# DRIVER_B.net
KiCad netlist of a schematic drawn in Altium Designer
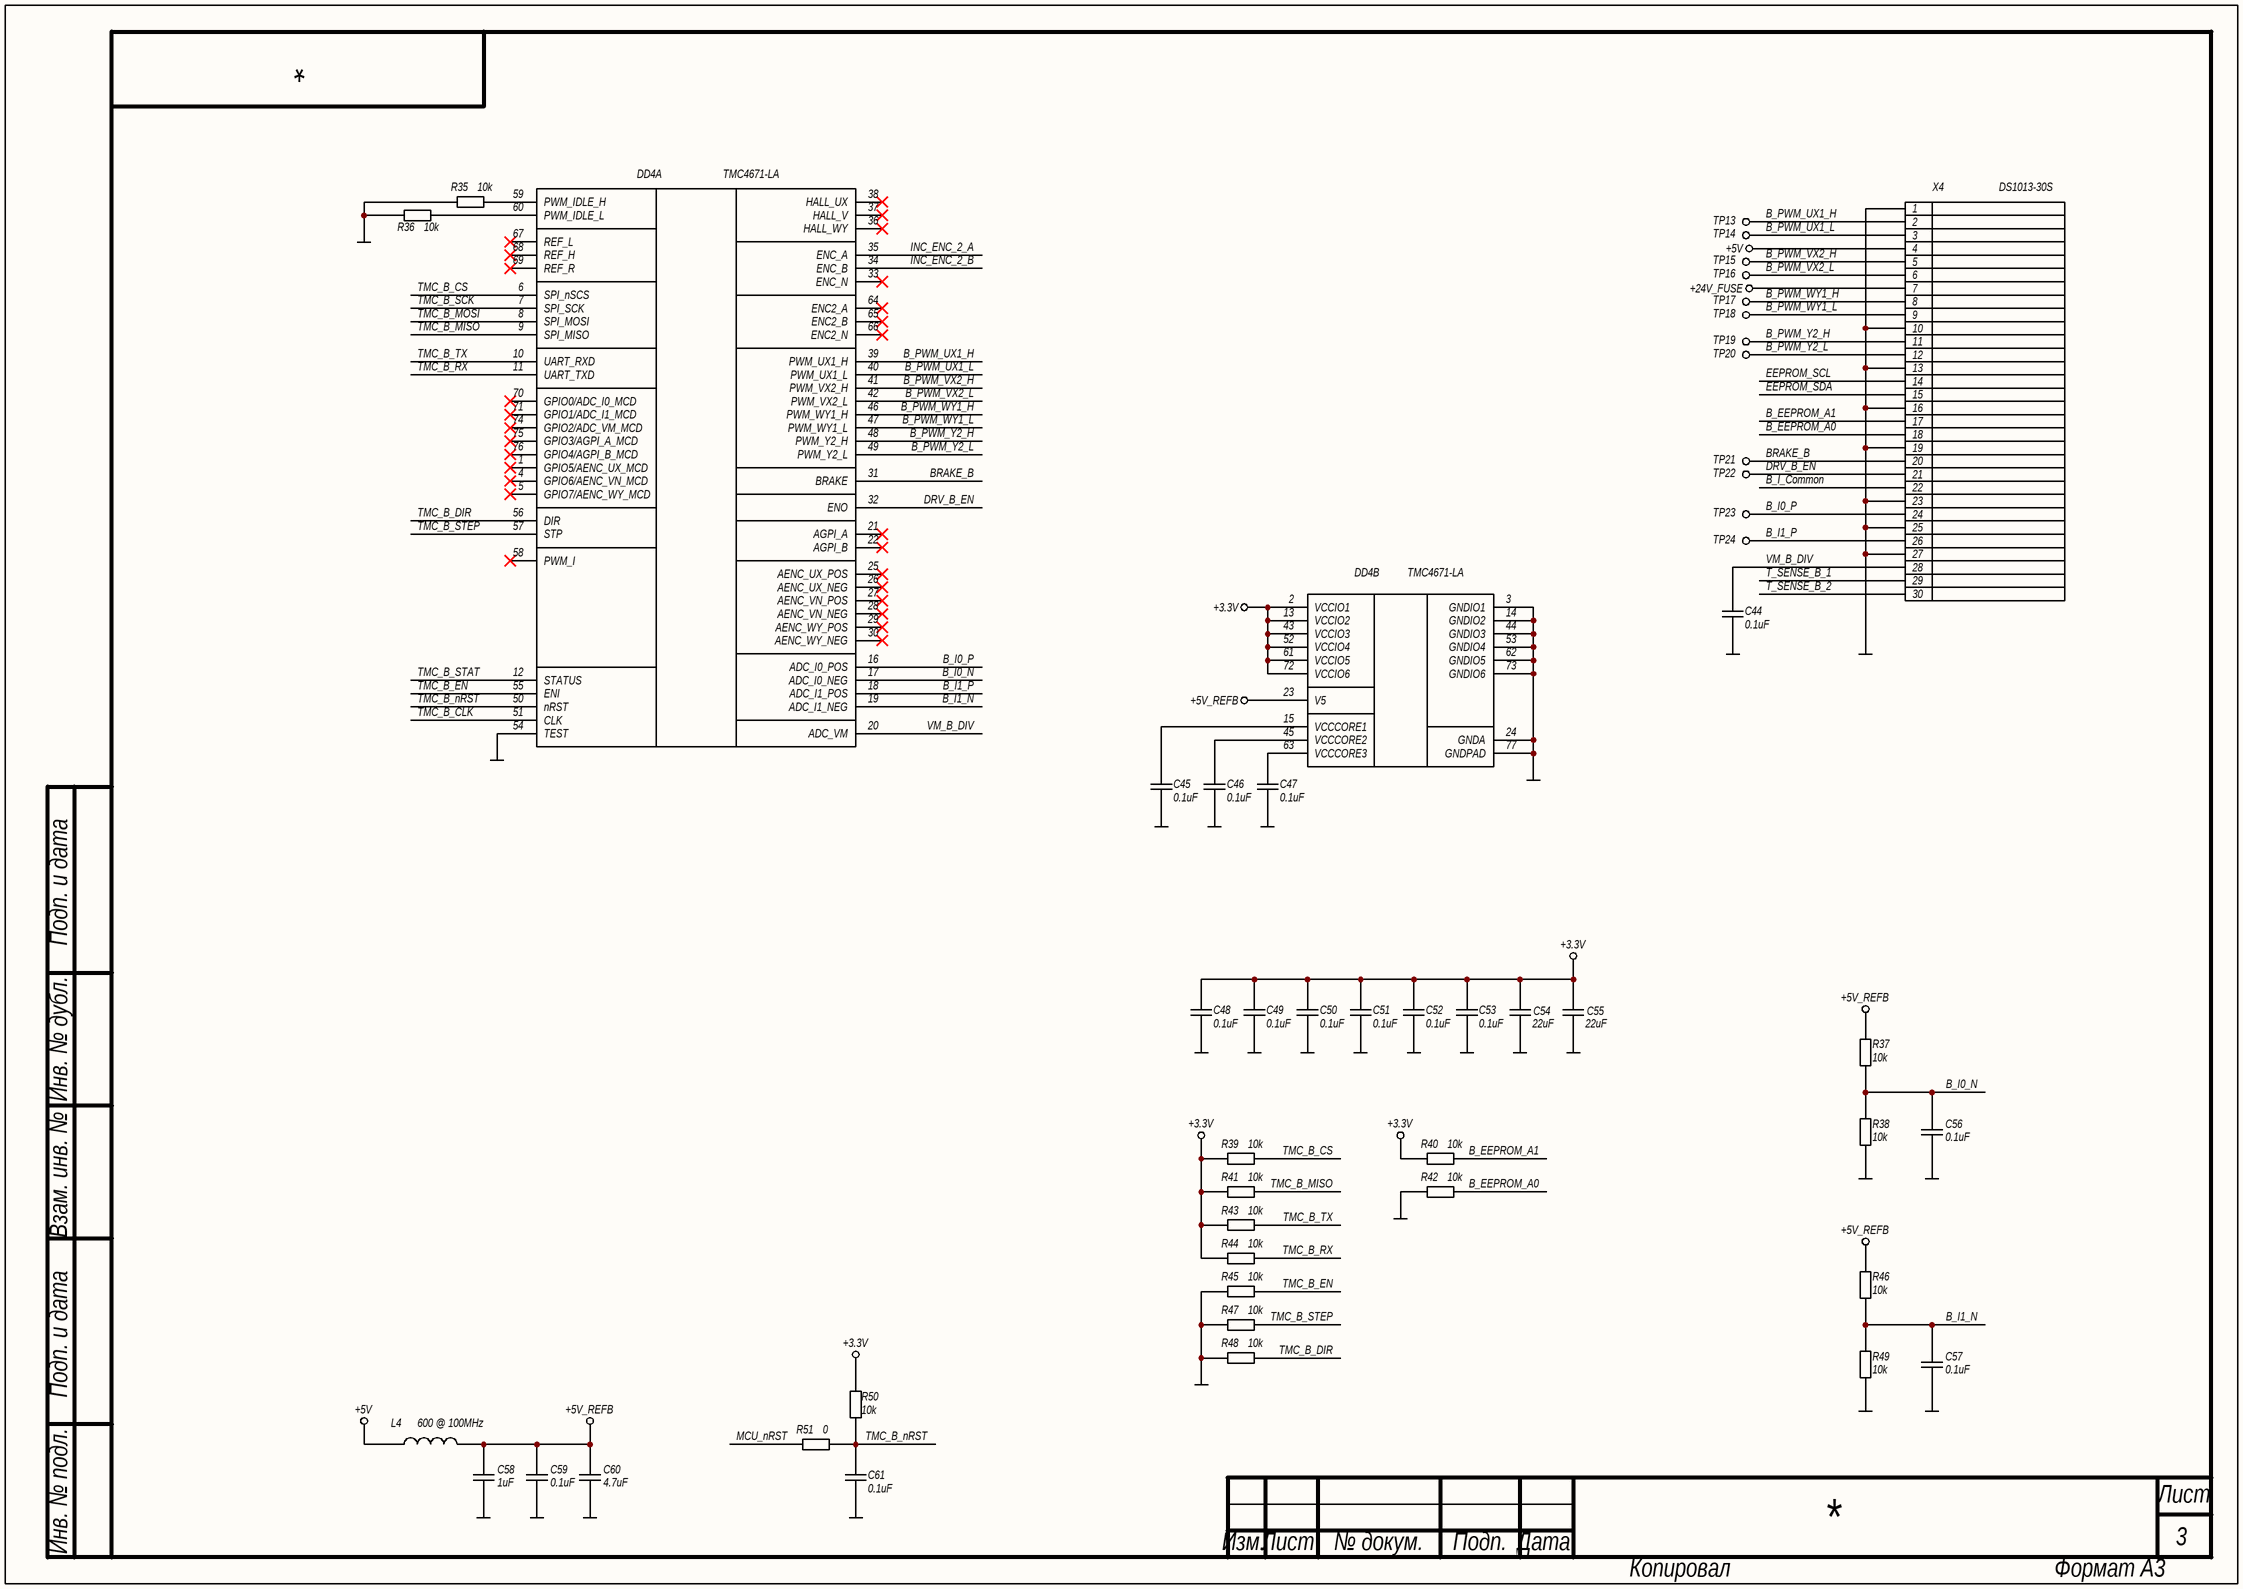
[diagram p0: DRIVER_B.SchDoc]

(export (version "E")
  (design (tool "Eeschema 10.0.6"))
  (components
    (comp (ref "C44")
      (value "0.1uF")
      (footprint "C0603N")
      (description "Конденсатор")
      (libsource (lib "Components Library") (part "CAP_FIXED"))
    )
    (comp (ref "C45")
      (value "0.1uF")
      (footprint "C0603N")
      (description "Конденсатор")
      (libsource (lib "Components Library") (part "CAP_FIXED"))
    )
    (comp (ref "C46")
      (value "0.1uF")
      (footprint "C0603N")
      (description "Конденсатор")
      (libsource (lib "Components Library") (part "CAP_FIXED"))
    )
    (comp (ref "C47")
      (value "0.1uF")
      (footprint "C0603N")
      (description "Конденсатор")
      (libsource (lib "Components Library") (part "CAP_FIXED"))
    )
    (comp (ref "C48")
      (value "0.1uF")
      (footprint "C0603N")
      (description "Конденсатор")
      (libsource (lib "Components Library") (part "CAP_FIXED"))
    )
    (comp (ref "C49")
      (value "0.1uF")
      (footprint "C0603N")
      (description "Конденсатор")
      (libsource (lib "Components Library") (part "CAP_FIXED"))
    )
    (comp (ref "C50")
      (value "0.1uF")
      (footprint "C0603N")
      (description "Конденсатор")
      (libsource (lib "Components Library") (part "CAP_FIXED"))
    )
    (comp (ref "C51")
      (value "0.1uF")
      (footprint "C0603N")
      (description "Конденсатор")
      (libsource (lib "Components Library") (part "CAP_FIXED"))
    )
    (comp (ref "C52")
      (value "0.1uF")
      (footprint "C0603N")
      (description "Конденсатор")
      (libsource (lib "Components Library") (part "CAP_FIXED"))
    )
    (comp (ref "C53")
      (value "0.1uF")
      (footprint "C0603N")
      (description "Конденсатор")
      (libsource (lib "Components Library") (part "CAP_FIXED"))
    )
    (comp (ref "C54")
      (value "22uF")
      (footprint "C0805N")
      (description "Конденсатор")
      (libsource (lib "Components Library") (part "CAP_FIXED"))
    )
    (comp (ref "C55")
      (value "22uF")
      (footprint "C0805N")
      (description "Конденсатор")
      (libsource (lib "Components Library") (part "CAP_FIXED"))
    )
    (comp (ref "C56")
      (value "0.1uF")
      (footprint "C0603N")
      (description "Конденсатор")
      (libsource (lib "Components Library") (part "CAP_FIXED"))
    )
    (comp (ref "C57")
      (value "0.1uF")
      (footprint "C0603N")
      (description "Конденсатор")
      (libsource (lib "Components Library") (part "CAP_FIXED"))
    )
    (comp (ref "C58")
      (value "1uF")
      (footprint "C0603N")
      (description "Конденсатор")
      (libsource (lib "Components Library") (part "CAP_FIXED"))
    )
    (comp (ref "C59")
      (value "0.1uF")
      (footprint "C0603N")
      (description "Конденсатор")
      (libsource (lib "Components Library") (part "CAP_FIXED"))
    )
    (comp (ref "C60")
      (value "4.7uF")
      (footprint "C0603N")
      (description "Конденсатор")
      (libsource (lib "Components Library") (part "CAP_FIXED"))
    )
    (comp (ref "C61")
      (value "0.1uF")
      (footprint "C0603N")
      (description "Конденсатор")
      (libsource (lib "Components Library") (part "CAP_FIXED"))
    )
    (comp (ref "DD4")
      (value "TMC4671-LA")
      (footprint "QFN76-EP")
      (description "Микросхема драйвер двигателя")
      (libsource (lib "Components Library") (part "TMC4671-LA"))
    )
    (comp (ref "L4")
      (value "600 @ 100MHz")
      (footprint "FB0603N")
      (description "Фильтр ЭМП индуктивный")
      (libsource (lib "Components Library") (part "IND_FILTER"))
    )
    (comp (ref "R35")
      (value "10k")
      (footprint "R0603N")
      (description "Резистор")
      (libsource (lib "Components Library") (part "RES_FIXED"))
    )
    (comp (ref "R36")
      (value "10k")
      (footprint "R0603N")
      (description "Резистор")
      (libsource (lib "Components Library") (part "RES_FIXED"))
    )
    (comp (ref "R37")
      (value "10k")
      (footprint "R0603N")
      (description "Резистор")
      (libsource (lib "") (part "RES_FIXED_1"))
    )
    (comp (ref "R38")
      (value "10k")
      (footprint "R0603N")
      (description "Резистор")
      (libsource (lib "") (part "RES_FIXED_1"))
    )
    (comp (ref "R39")
      (value "10k")
      (footprint "R0603N")
      (description "Резистор")
      (libsource (lib "Components Library") (part "RES_FIXED"))
    )
    (comp (ref "R40")
      (value "10k")
      (footprint "R0603N")
      (description "Резистор")
      (libsource (lib "Components Library") (part "RES_FIXED"))
    )
    (comp (ref "R41")
      (value "10k")
      (footprint "R0603N")
      (description "Резистор")
      (libsource (lib "Components Library") (part "RES_FIXED"))
    )
    (comp (ref "R42")
      (value "10k")
      (footprint "R0603N")
      (description "Резистор")
      (libsource (lib "Components Library") (part "RES_FIXED"))
    )
    (comp (ref "R43")
      (value "10k")
      (footprint "R0603N")
      (description "Резистор")
      (libsource (lib "Components Library") (part "RES_FIXED"))
    )
    (comp (ref "R44")
      (value "10k")
      (footprint "R0603N")
      (description "Резистор")
      (libsource (lib "Components Library") (part "RES_FIXED"))
    )
    (comp (ref "R45")
      (value "10k")
      (footprint "R0603N")
      (description "Резистор")
      (libsource (lib "Components Library") (part "RES_FIXED"))
    )
    (comp (ref "R46")
      (value "10k")
      (footprint "R0603N")
      (description "Резистор")
      (libsource (lib "") (part "RES_FIXED_1"))
    )
    (comp (ref "R47")
      (value "10k")
      (footprint "R0603N")
      (description "Резистор")
      (libsource (lib "Components Library") (part "RES_FIXED"))
    )
    (comp (ref "R48")
      (value "10k")
      (footprint "R0603N")
      (description "Резистор")
      (libsource (lib "Components Library") (part "RES_FIXED"))
    )
    (comp (ref "R49")
      (value "10k")
      (footprint "R0603N")
      (description "Резистор")
      (libsource (lib "") (part "RES_FIXED_1"))
    )
    (comp (ref "R50")
      (value "10k")
      (footprint "R0603N")
      (description "Резистор")
      (libsource (lib "") (part "RES_FIXED_1"))
    )
    (comp (ref "R51")
      (value "0")
      (footprint "R0603N")
      (description "Резистор")
      (libsource (lib "Components Library") (part "RES_FIXED"))
    )
    (comp (ref "TP13")
      (value "TEST_POINT")
      (footprint "TP_RPAD_0.8MM")
      (description "Контрольная точка")
      (libsource (lib "Components Library") (part "TEST_POINT"))
    )
    (comp (ref "TP14")
      (value "TEST_POINT")
      (footprint "TP_RPAD_0.8MM")
      (description "Контрольная точка")
      (libsource (lib "Components Library") (part "TEST_POINT"))
    )
    (comp (ref "TP15")
      (value "TEST_POINT")
      (footprint "TP_RPAD_0.8MM")
      (description "Контрольная точка")
      (libsource (lib "Components Library") (part "TEST_POINT"))
    )
    (comp (ref "TP16")
      (value "TEST_POINT")
      (footprint "TP_RPAD_0.8MM")
      (description "Контрольная точка")
      (libsource (lib "Components Library") (part "TEST_POINT"))
    )
    (comp (ref "TP17")
      (value "TEST_POINT")
      (footprint "TP_RPAD_0.8MM")
      (description "Контрольная точка")
      (libsource (lib "Components Library") (part "TEST_POINT"))
    )
    (comp (ref "TP18")
      (value "TEST_POINT")
      (footprint "TP_RPAD_0.8MM")
      (description "Контрольная точка")
      (libsource (lib "Components Library") (part "TEST_POINT"))
    )
    (comp (ref "TP19")
      (value "TEST_POINT")
      (footprint "TP_RPAD_0.8MM")
      (description "Контрольная точка")
      (libsource (lib "Components Library") (part "TEST_POINT"))
    )
    (comp (ref "TP20")
      (value "TEST_POINT")
      (footprint "TP_RPAD_0.8MM")
      (description "Контрольная точка")
      (libsource (lib "Components Library") (part "TEST_POINT"))
    )
    (comp (ref "TP21")
      (value "TEST_POINT")
      (footprint "TP_RPAD_0.8MM")
      (description "Контрольная точка")
      (libsource (lib "Components Library") (part "TEST_POINT"))
    )
    (comp (ref "TP22")
      (value "TEST_POINT")
      (footprint "TP_RPAD_0.8MM")
      (description "Контрольная точка")
      (libsource (lib "Components Library") (part "TEST_POINT"))
    )
    (comp (ref "TP23")
      (value "TEST_POINT")
      (footprint "TP_RPAD_0.8MM")
      (description "Контрольная точка")
      (libsource (lib "Components Library") (part "TEST_POINT"))
    )
    (comp (ref "TP24")
      (value "TEST_POINT")
      (footprint "TP_RPAD_0.8MM")
      (description "Контрольная точка")
      (libsource (lib "Components Library") (part "TEST_POINT"))
    )
    (comp (ref "X4")
      (value "DS1013-30S")
      (footprint "2.54_2X15_HEADER_BOX")
      (description "Разъем, 30 контактов")
      (libsource (lib "Components Library") (part "Connector 30"))
    )
  )
  (nets
    (net (code "1") (name "+3.3V") (class "Default")
      (node (ref "C48") (pin "2") (pinfunction "2_2") (pintype "passive"))
      (node (ref "C49") (pin "2") (pinfunction "2_2") (pintype "passive"))
      (node (ref "C50") (pin "2") (pinfunction "2_2") (pintype "passive"))
      (node (ref "C51") (pin "2") (pinfunction "2_2") (pintype "passive"))
      (node (ref "C52") (pin "2") (pinfunction "2_2") (pintype "passive"))
      (node (ref "C53") (pin "2") (pinfunction "2_2") (pintype "passive"))
      (node (ref "C54") (pin "2") (pinfunction "2_2") (pintype "passive"))
      (node (ref "C55") (pin "2") (pinfunction "2_2") (pintype "passive"))
      (node (ref "DD4") (pin "13") (pinfunction "VCCIO2_13") (pintype "power_in"))
      (node (ref "DD4") (pin "2") (pinfunction "VCCIO1_2") (pintype "power_in"))
      (node (ref "DD4") (pin "43") (pinfunction "VCCIO3_43") (pintype "power_in"))
      (node (ref "DD4") (pin "52") (pinfunction "VCCIO4_52") (pintype "power_in"))
      (node (ref "DD4") (pin "61") (pinfunction "VCCIO5_61") (pintype "power_in"))
      (node (ref "DD4") (pin "72") (pinfunction "VCCIO6_72") (pintype "power_in"))
      (node (ref "R39") (pin "2") (pinfunction "2_2") (pintype "passive"))
      (node (ref "R40") (pin "2") (pinfunction "2_2") (pintype "passive"))
      (node (ref "R41") (pin "2") (pinfunction "2_2") (pintype "passive"))
      (node (ref "R43") (pin "2") (pinfunction "2_2") (pintype "passive"))
      (node (ref "R44") (pin "2") (pinfunction "2_2") (pintype "passive"))
      (node (ref "R50") (pin "2") (pinfunction "2_2") (pintype "passive"))
    )
    (net (code "2") (name "+5V") (class "Default")
      (node (ref "L4") (pin "1") (pinfunction "1_1") (pintype "passive"))
      (node (ref "X4") (pin "4") (pinfunction "4_4") (pintype "power_in"))
    )
    (net (code "3") (name "+5V_REFB") (class "Default")
      (node (ref "C58") (pin "2") (pinfunction "2_2") (pintype "passive"))
      (node (ref "C59") (pin "2") (pinfunction "2_2") (pintype "passive"))
      (node (ref "C60") (pin "2") (pinfunction "2_2") (pintype "passive"))
      (node (ref "DD4") (pin "23") (pinfunction "V5_23") (pintype "power_in"))
      (node (ref "L4") (pin "2") (pinfunction "2_2") (pintype "passive"))
      (node (ref "R37") (pin "2") (pinfunction "2_2") (pintype "passive"))
      (node (ref "R46") (pin "2") (pinfunction "2_2") (pintype "passive"))
    )
    (net (code "4") (name "+24V_FUSE") (class "Default")
      (node (ref "X4") (pin "7") (pinfunction "7_7") (pintype "power_in"))
    )
    (net (code "5") (name "/BRAKE_B") (class "Default")
      (node (ref "DD4") (pin "31") (pinfunction "BRAKE_31") (pintype "power_in"))
      (node (ref "TP21") (pin "1") (pinfunction "1_1") (pintype "passive"))
      (node (ref "X4") (pin "20") (pinfunction "20_20") (pintype "power_in"))
    )
    (net (code "6") (name "/B_EEPROM_A0") (class "Default")
      (node (ref "R42") (pin "1") (pinfunction "1_1") (pintype "passive"))
      (node (ref "X4") (pin "18") (pinfunction "18_18") (pintype "power_in"))
    )
    (net (code "7") (name "/B_EEPROM_A1") (class "Default")
      (node (ref "R40") (pin "1") (pinfunction "1_1") (pintype "passive"))
      (node (ref "X4") (pin "17") (pinfunction "17_17") (pintype "power_in"))
    )
    (net (code "8") (name "/B_I0_N") (class "Default")
      (node (ref "C56") (pin "2") (pinfunction "2_2") (pintype "passive"))
      (node (ref "DD4") (pin "17") (pinfunction "ADC_I0_NEG_17") (pintype "power_in"))
      (node (ref "R37") (pin "1") (pinfunction "1_1") (pintype "passive"))
      (node (ref "R38") (pin "2") (pinfunction "2_2") (pintype "passive"))
    )
    (net (code "9") (name "/B_I0_P") (class "Default")
      (node (ref "DD4") (pin "16") (pinfunction "ADC_I0_POS_16") (pintype "power_in"))
      (node (ref "TP23") (pin "1") (pinfunction "1_1") (pintype "passive"))
      (node (ref "X4") (pin "24") (pinfunction "24_24") (pintype "power_in"))
    )
    (net (code "10") (name "/B_I1_N") (class "Default")
      (node (ref "C57") (pin "2") (pinfunction "2_2") (pintype "passive"))
      (node (ref "DD4") (pin "19") (pinfunction "ADC_I1_NEG_19") (pintype "power_in"))
      (node (ref "R46") (pin "1") (pinfunction "1_1") (pintype "passive"))
      (node (ref "R49") (pin "2") (pinfunction "2_2") (pintype "passive"))
    )
    (net (code "11") (name "/B_I1_P") (class "Default")
      (node (ref "DD4") (pin "18") (pinfunction "ADC_I1_POS_18") (pintype "power_in"))
      (node (ref "TP24") (pin "1") (pinfunction "1_1") (pintype "passive"))
      (node (ref "X4") (pin "26") (pinfunction "26_26") (pintype "power_in"))
    )
    (net (code "12") (name "/B_I_Common") (class "Default")
      (node (ref "X4") (pin "22") (pinfunction "22_22") (pintype "power_in"))
    )
    (net (code "13") (name "/B_PWM_UX1_H") (class "Default")
      (node (ref "DD4") (pin "39") (pinfunction "PWM_UX1_H_39") (pintype "power_in"))
      (node (ref "TP13") (pin "1") (pinfunction "1_1") (pintype "passive"))
      (node (ref "X4") (pin "2") (pinfunction "2_2") (pintype "power_in"))
    )
    (net (code "14") (name "/B_PWM_UX1_L") (class "Default")
      (node (ref "DD4") (pin "40") (pinfunction "PWM_UX1_L_40") (pintype "power_in"))
      (node (ref "TP14") (pin "1") (pinfunction "1_1") (pintype "passive"))
      (node (ref "X4") (pin "3") (pinfunction "3_3") (pintype "power_in"))
    )
    (net (code "15") (name "/B_PWM_VX2_H") (class "Default")
      (node (ref "DD4") (pin "41") (pinfunction "PWM_VX2_H_41") (pintype "power_in"))
      (node (ref "TP15") (pin "1") (pinfunction "1_1") (pintype "passive"))
      (node (ref "X4") (pin "5") (pinfunction "5_5") (pintype "power_in"))
    )
    (net (code "16") (name "/B_PWM_VX2_L") (class "Default")
      (node (ref "DD4") (pin "42") (pinfunction "PWM_VX2_L_42") (pintype "power_in"))
      (node (ref "TP16") (pin "1") (pinfunction "1_1") (pintype "passive"))
      (node (ref "X4") (pin "6") (pinfunction "6_6") (pintype "power_in"))
    )
    (net (code "17") (name "/B_PWM_WY1_H") (class "Default")
      (node (ref "DD4") (pin "46") (pinfunction "PWM_WY1_H_46") (pintype "power_in"))
      (node (ref "TP17") (pin "1") (pinfunction "1_1") (pintype "passive"))
      (node (ref "X4") (pin "8") (pinfunction "8_8") (pintype "power_in"))
    )
    (net (code "18") (name "/B_PWM_WY1_L") (class "Default")
      (node (ref "DD4") (pin "47") (pinfunction "PWM_WY1_L_47") (pintype "power_in"))
      (node (ref "TP18") (pin "1") (pinfunction "1_1") (pintype "passive"))
      (node (ref "X4") (pin "9") (pinfunction "9_9") (pintype "power_in"))
    )
    (net (code "19") (name "/B_PWM_Y2_H") (class "Default")
      (node (ref "DD4") (pin "48") (pinfunction "PWM_Y2_H_48") (pintype "power_in"))
      (node (ref "TP19") (pin "1") (pinfunction "1_1") (pintype "passive"))
      (node (ref "X4") (pin "11") (pinfunction "11_11") (pintype "power_in"))
    )
    (net (code "20") (name "/B_PWM_Y2_L") (class "Default")
      (node (ref "DD4") (pin "49") (pinfunction "PWM_Y2_L_49") (pintype "power_in"))
      (node (ref "TP20") (pin "1") (pinfunction "1_1") (pintype "passive"))
      (node (ref "X4") (pin "12") (pinfunction "12_12") (pintype "power_in"))
    )
    (net (code "21") (name "/DRV_B_EN") (class "Default")
      (node (ref "DD4") (pin "32") (pinfunction "ENO_32") (pintype "power_in"))
      (node (ref "TP22") (pin "1") (pinfunction "1_1") (pintype "passive"))
      (node (ref "X4") (pin "21") (pinfunction "21_21") (pintype "power_in"))
    )
    (net (code "22") (name "/EEPROM_SCL") (class "Default")
      (node (ref "X4") (pin "14") (pinfunction "14_14") (pintype "power_in"))
    )
    (net (code "23") (name "/EEPROM_SDA") (class "Default")
      (node (ref "X4") (pin "15") (pinfunction "15_15") (pintype "power_in"))
    )
    (net (code "24") (name "/INC_ENC_2_A") (class "Default")
      (node (ref "DD4") (pin "35") (pinfunction "ENC_A_35") (pintype "power_in"))
    )
    (net (code "25") (name "/INC_ENC_2_B") (class "Default")
      (node (ref "DD4") (pin "34") (pinfunction "ENC_B_34") (pintype "power_in"))
    )
    (net (code "26") (name "/MCU_nRST") (class "Default")
      (node (ref "R51") (pin "2") (pinfunction "2_2") (pintype "passive"))
    )
    (net (code "27") (name "/TMC_B_CLK") (class "Default")
      (node (ref "DD4") (pin "51") (pinfunction "CLK_51") (pintype "power_in"))
    )
    (net (code "28") (name "/TMC_B_CS") (class "Default")
      (node (ref "DD4") (pin "6") (pinfunction "SPI_nSCS_6") (pintype "power_in"))
      (node (ref "R39") (pin "1") (pinfunction "1_1") (pintype "passive"))
    )
    (net (code "29") (name "/TMC_B_DIR") (class "Default")
      (node (ref "DD4") (pin "56") (pinfunction "DIR_56") (pintype "power_in"))
      (node (ref "R48") (pin "1") (pinfunction "1_1") (pintype "passive"))
    )
    (net (code "30") (name "/TMC_B_EN") (class "Default")
      (node (ref "DD4") (pin "55") (pinfunction "ENI_55") (pintype "power_in"))
      (node (ref "R45") (pin "1") (pinfunction "1_1") (pintype "passive"))
    )
    (net (code "31") (name "/TMC_B_MISO") (class "Default")
      (node (ref "DD4") (pin "9") (pinfunction "SPI_MISO_9") (pintype "power_in"))
      (node (ref "R41") (pin "1") (pinfunction "1_1") (pintype "passive"))
    )
    (net (code "32") (name "/TMC_B_MOSI") (class "Default")
      (node (ref "DD4") (pin "8") (pinfunction "SPI_MOSI_8") (pintype "power_in"))
    )
    (net (code "33") (name "/TMC_B_RX") (class "Default")
      (node (ref "DD4") (pin "11") (pinfunction "UART_TXD_11") (pintype "power_in"))
      (node (ref "R44") (pin "1") (pinfunction "1_1") (pintype "passive"))
    )
    (net (code "34") (name "/TMC_B_SCK") (class "Default")
      (node (ref "DD4") (pin "7") (pinfunction "SPI_SCK_7") (pintype "power_in"))
    )
    (net (code "35") (name "/TMC_B_STAT") (class "Default")
      (node (ref "DD4") (pin "12") (pinfunction "STATUS_12") (pintype "power_in"))
    )
    (net (code "36") (name "/TMC_B_STEP") (class "Default")
      (node (ref "DD4") (pin "57") (pinfunction "STP_57") (pintype "power_in"))
      (node (ref "R47") (pin "1") (pinfunction "1_1") (pintype "passive"))
    )
    (net (code "37") (name "/TMC_B_TX") (class "Default")
      (node (ref "DD4") (pin "10") (pinfunction "UART_RXD_10") (pintype "power_in"))
      (node (ref "R43") (pin "1") (pinfunction "1_1") (pintype "passive"))
    )
    (net (code "38") (name "/TMC_B_nRST") (class "Default")
      (node (ref "C61") (pin "2") (pinfunction "2_2") (pintype "passive"))
      (node (ref "DD4") (pin "50") (pinfunction "nRST_50") (pintype "power_in"))
      (node (ref "R50") (pin "1") (pinfunction "1_1") (pintype "passive"))
      (node (ref "R51") (pin "1") (pinfunction "1_1") (pintype "passive"))
    )
    (net (code "39") (name "/T_SENSE_B_1") (class "Default")
      (node (ref "X4") (pin "29") (pinfunction "29_29") (pintype "power_in"))
    )
    (net (code "40") (name "/T_SENSE_B_2") (class "Default")
      (node (ref "X4") (pin "30") (pinfunction "30_30") (pintype "power_in"))
    )
    (net (code "41") (name "/VM_B_DIV") (class "Default")
      (node (ref "C44") (pin "2") (pinfunction "2_2") (pintype "passive"))
      (node (ref "DD4") (pin "20") (pinfunction "ADC_VM_20") (pintype "power_in"))
      (node (ref "X4") (pin "28") (pinfunction "28_28") (pintype "power_in"))
    )
    (net (code "42") (name "GND") (class "Default")
      (node (ref "C44") (pin "1") (pinfunction "1_1") (pintype "passive"))
      (node (ref "C45") (pin "1") (pinfunction "1_1") (pintype "passive"))
      (node (ref "C46") (pin "1") (pinfunction "1_1") (pintype "passive"))
      (node (ref "C47") (pin "1") (pinfunction "1_1") (pintype "passive"))
      (node (ref "C48") (pin "1") (pinfunction "1_1") (pintype "passive"))
      (node (ref "C49") (pin "1") (pinfunction "1_1") (pintype "passive"))
      (node (ref "C50") (pin "1") (pinfunction "1_1") (pintype "passive"))
      (node (ref "C51") (pin "1") (pinfunction "1_1") (pintype "passive"))
      (node (ref "C52") (pin "1") (pinfunction "1_1") (pintype "passive"))
      (node (ref "C53") (pin "1") (pinfunction "1_1") (pintype "passive"))
      (node (ref "C54") (pin "1") (pinfunction "1_1") (pintype "passive"))
      (node (ref "C55") (pin "1") (pinfunction "1_1") (pintype "passive"))
      (node (ref "C56") (pin "1") (pinfunction "1_1") (pintype "passive"))
      (node (ref "C57") (pin "1") (pinfunction "1_1") (pintype "passive"))
      (node (ref "C58") (pin "1") (pinfunction "1_1") (pintype "passive"))
      (node (ref "C59") (pin "1") (pinfunction "1_1") (pintype "passive"))
      (node (ref "C60") (pin "1") (pinfunction "1_1") (pintype "passive"))
      (node (ref "C61") (pin "1") (pinfunction "1_1") (pintype "passive"))
      (node (ref "DD4") (pin "14") (pinfunction "GNDIO2_14") (pintype "power_in"))
      (node (ref "DD4") (pin "24") (pinfunction "GNDA_24") (pintype "power_in"))
      (node (ref "DD4") (pin "3") (pinfunction "GNDIO1_3") (pintype "power_in"))
      (node (ref "DD4") (pin "44") (pinfunction "GNDIO3_44") (pintype "power_in"))
      (node (ref "DD4") (pin "53") (pinfunction "GNDIO4_53") (pintype "power_in"))
      (node (ref "DD4") (pin "54") (pinfunction "TEST_54") (pintype "power_in"))
      (node (ref "DD4") (pin "62") (pinfunction "GNDIO5_62") (pintype "power_in"))
      (node (ref "DD4") (pin "73") (pinfunction "GNDIO6_73") (pintype "power_in"))
      (node (ref "DD4") (pin "77") (pinfunction "GNDPAD_77") (pintype "power_in"))
      (node (ref "R35") (pin "2") (pinfunction "2_2") (pintype "passive"))
      (node (ref "R36") (pin "2") (pinfunction "2_2") (pintype "passive"))
      (node (ref "R38") (pin "1") (pinfunction "1_1") (pintype "passive"))
      (node (ref "R42") (pin "2") (pinfunction "2_2") (pintype "passive"))
      (node (ref "R45") (pin "2") (pinfunction "2_2") (pintype "passive"))
      (node (ref "R47") (pin "2") (pinfunction "2_2") (pintype "passive"))
      (node (ref "R48") (pin "2") (pinfunction "2_2") (pintype "passive"))
      (node (ref "R49") (pin "1") (pinfunction "1_1") (pintype "passive"))
      (node (ref "X4") (pin "1") (pinfunction "1_1") (pintype "power_in"))
      (node (ref "X4") (pin "10") (pinfunction "10_10") (pintype "power_in"))
      (node (ref "X4") (pin "13") (pinfunction "13_13") (pintype "power_in"))
      (node (ref "X4") (pin "16") (pinfunction "16_16") (pintype "power_in"))
      (node (ref "X4") (pin "19") (pinfunction "19_19") (pintype "power_in"))
      (node (ref "X4") (pin "23") (pinfunction "23_23") (pintype "power_in"))
      (node (ref "X4") (pin "25") (pinfunction "25_25") (pintype "power_in"))
      (node (ref "X4") (pin "27") (pinfunction "27_27") (pintype "power_in"))
    )
    (net (code "43") (name "Net-(DD4A-PWM_IDLE_H)") (class "Default")
      (node (ref "DD4") (pin "59") (pinfunction "PWM_IDLE_H_59") (pintype "power_in"))
      (node (ref "R35") (pin "1") (pinfunction "1_1") (pintype "passive"))
    )
    (net (code "44") (name "Net-(DD4A-PWM_IDLE_L)") (class "Default")
      (node (ref "DD4") (pin "60") (pinfunction "PWM_IDLE_L_60") (pintype "power_in"))
      (node (ref "R36") (pin "1") (pinfunction "1_1") (pintype "passive"))
    )
    (net (code "45") (name "Net-(DD4B-VCCCORE1)") (class "Default")
      (node (ref "C45") (pin "2") (pinfunction "2_2") (pintype "passive"))
      (node (ref "DD4") (pin "15") (pinfunction "VCCCORE1_15") (pintype "power_in"))
    )
    (net (code "46") (name "Net-(DD4B-VCCCORE2)") (class "Default")
      (node (ref "C46") (pin "2") (pinfunction "2_2") (pintype "passive"))
      (node (ref "DD4") (pin "45") (pinfunction "VCCCORE2_45") (pintype "power_in"))
    )
    (net (code "47") (name "Net-(DD4B-VCCCORE3)") (class "Default")
      (node (ref "C47") (pin "2") (pinfunction "2_2") (pintype "passive"))
      (node (ref "DD4") (pin "63") (pinfunction "VCCCORE3_63") (pintype "power_in"))
    )
    (net (code "48") (name "unconnected-(DD4A-AENC_UX_NEG-Pad26)") (class "Default")
      (node (ref "DD4") (pin "26") (pinfunction "AENC_UX_NEG_26") (pintype "power_in+no_connect"))
    )
    (net (code "49") (name "unconnected-(DD4A-AENC_UX_POS-Pad25)") (class "Default")
      (node (ref "DD4") (pin "25") (pinfunction "AENC_UX_POS_25") (pintype "power_in+no_connect"))
    )
    (net (code "50") (name "unconnected-(DD4A-AENC_VN_NEG-Pad28)") (class "Default")
      (node (ref "DD4") (pin "28") (pinfunction "AENC_VN_NEG_28") (pintype "power_in+no_connect"))
    )
    (net (code "51") (name "unconnected-(DD4A-AENC_VN_POS-Pad27)") (class "Default")
      (node (ref "DD4") (pin "27") (pinfunction "AENC_VN_POS_27") (pintype "power_in+no_connect"))
    )
    (net (code "52") (name "unconnected-(DD4A-AENC_WY_NEG-Pad30)") (class "Default")
      (node (ref "DD4") (pin "30") (pinfunction "AENC_WY_NEG_30") (pintype "power_in+no_connect"))
    )
    (net (code "53") (name "unconnected-(DD4A-AENC_WY_POS-Pad29)") (class "Default")
      (node (ref "DD4") (pin "29") (pinfunction "AENC_WY_POS_29") (pintype "power_in+no_connect"))
    )
    (net (code "54") (name "unconnected-(DD4A-AGPI_A-Pad21)") (class "Default")
      (node (ref "DD4") (pin "21") (pinfunction "AGPI_A_21") (pintype "power_in+no_connect"))
    )
    (net (code "55") (name "unconnected-(DD4A-AGPI_B-Pad22)") (class "Default")
      (node (ref "DD4") (pin "22") (pinfunction "AGPI_B_22") (pintype "power_in+no_connect"))
    )
    (net (code "56") (name "unconnected-(DD4A-ENC2_A-Pad64)") (class "Default")
      (node (ref "DD4") (pin "64") (pinfunction "ENC2_A_64") (pintype "power_in+no_connect"))
    )
    (net (code "57") (name "unconnected-(DD4A-ENC2_B-Pad65)") (class "Default")
      (node (ref "DD4") (pin "65") (pinfunction "ENC2_B_65") (pintype "power_in+no_connect"))
    )
    (net (code "58") (name "unconnected-(DD4A-ENC2_N-Pad66)") (class "Default")
      (node (ref "DD4") (pin "66") (pinfunction "ENC2_N_66") (pintype "power_in+no_connect"))
    )
    (net (code "59") (name "unconnected-(DD4A-ENC_N-Pad33)") (class "Default")
      (node (ref "DD4") (pin "33") (pinfunction "ENC_N_33") (pintype "power_in+no_connect"))
    )
    (net (code "60") (name "unconnected-(DD4A-GPIO0{slash}ADC_I0_MCD-Pad70)") (class "Default")
      (node (ref "DD4") (pin "70") (pinfunction "GPIO0/ADC_I0_MCD_70") (pintype "power_in+no_connect"))
    )
    (net (code "61") (name "unconnected-(DD4A-GPIO1{slash}ADC_I1_MCD-Pad71)") (class "Default")
      (node (ref "DD4") (pin "71") (pinfunction "GPIO1/ADC_I1_MCD_71") (pintype "power_in+no_connect"))
    )
    (net (code "62") (name "unconnected-(DD4A-GPIO2{slash}ADC_VM_MCD-Pad74)") (class "Default")
      (node (ref "DD4") (pin "74") (pinfunction "GPIO2/ADC_VM_MCD_74") (pintype "power_in+no_connect"))
    )
    (net (code "63") (name "unconnected-(DD4A-GPIO3{slash}AGPI_A_MCD-Pad75)") (class "Default")
      (node (ref "DD4") (pin "75") (pinfunction "GPIO3/AGPI_A_MCD_75") (pintype "power_in+no_connect"))
    )
    (net (code "64") (name "unconnected-(DD4A-GPIO4{slash}AGPI_B_MCD-Pad76)") (class "Default")
      (node (ref "DD4") (pin "76") (pinfunction "GPIO4/AGPI_B_MCD_76") (pintype "power_in+no_connect"))
    )
    (net (code "65") (name "unconnected-(DD4A-GPIO5{slash}AENC_UX_MCD-Pad1)") (class "Default")
      (node (ref "DD4") (pin "1") (pinfunction "GPIO5/AENC_UX_MCD_1") (pintype "power_in+no_connect"))
    )
    (net (code "66") (name "unconnected-(DD4A-GPIO6{slash}AENC_VN_MCD-Pad4)") (class "Default")
      (node (ref "DD4") (pin "4") (pinfunction "GPIO6/AENC_VN_MCD_4") (pintype "power_in+no_connect"))
    )
    (net (code "67") (name "unconnected-(DD4A-GPIO7{slash}AENC_WY_MCD-Pad5)") (class "Default")
      (node (ref "DD4") (pin "5") (pinfunction "GPIO7/AENC_WY_MCD_5") (pintype "power_in+no_connect"))
    )
    (net (code "68") (name "unconnected-(DD4A-HALL_UX-Pad38)") (class "Default")
      (node (ref "DD4") (pin "38") (pinfunction "HALL_UX_38") (pintype "power_in+no_connect"))
    )
    (net (code "69") (name "unconnected-(DD4A-HALL_V-Pad37)") (class "Default")
      (node (ref "DD4") (pin "37") (pinfunction "HALL_V_37") (pintype "power_in+no_connect"))
    )
    (net (code "70") (name "unconnected-(DD4A-HALL_WY-Pad36)") (class "Default")
      (node (ref "DD4") (pin "36") (pinfunction "HALL_WY_36") (pintype "power_in+no_connect"))
    )
    (net (code "71") (name "unconnected-(DD4A-PWM_I-Pad58)") (class "Default")
      (node (ref "DD4") (pin "58") (pinfunction "PWM_I_58") (pintype "power_in+no_connect"))
    )
    (net (code "72") (name "unconnected-(DD4A-REF_H-Pad68)") (class "Default")
      (node (ref "DD4") (pin "68") (pinfunction "REF_H_68") (pintype "power_in+no_connect"))
    )
    (net (code "73") (name "unconnected-(DD4A-REF_L-Pad67)") (class "Default")
      (node (ref "DD4") (pin "67") (pinfunction "REF_L_67") (pintype "power_in+no_connect"))
    )
    (net (code "74") (name "unconnected-(DD4A-REF_R-Pad69)") (class "Default")
      (node (ref "DD4") (pin "69") (pinfunction "REF_R_69") (pintype "power_in+no_connect"))
    )
  )
)
